# 2_4_-V1.net
KiCad netlist of a schematic drawn in Altium Designer
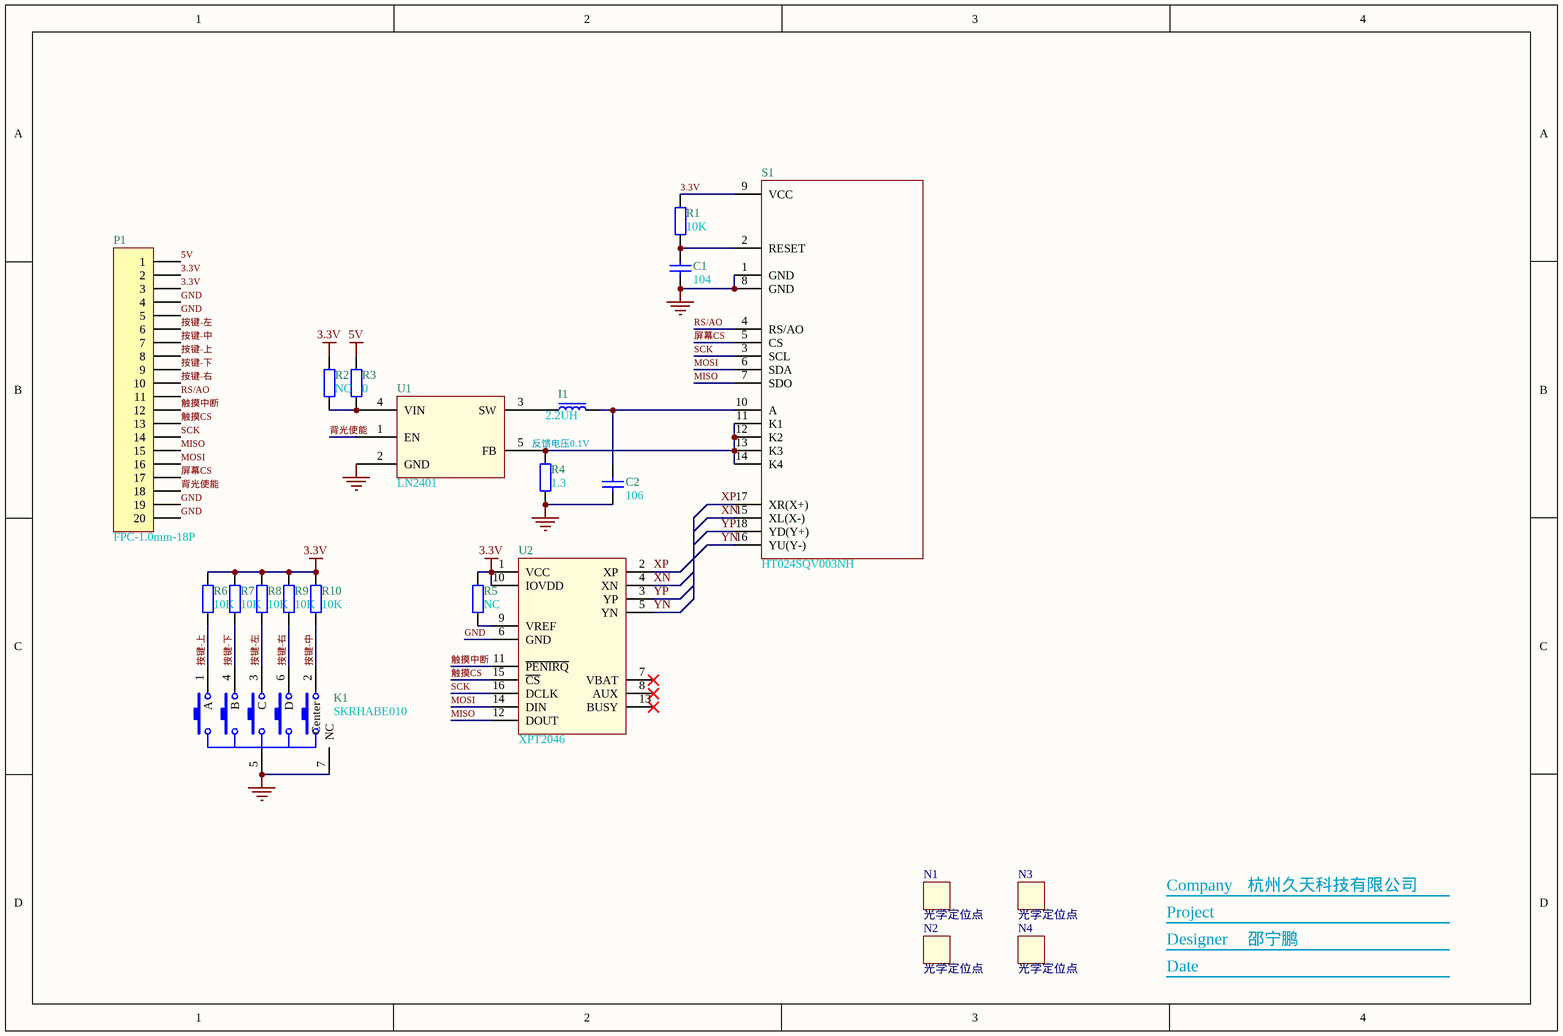
[diagram p0: 2.4寸液晶屏-V1.SchDoc]

(export (version "E")
  (design (tool "Eeschema 10.0.6"))
  (components
    (comp (ref "C1")
      (value "104")
      (footprint "C-0603")
      (description "0805")
      (fields (field (name "PUBLISHER") "Altium Limited"))
      (libsource (lib "2电容-V1.0") (part "Cap-0603"))
    )
    (comp (ref "C2")
      (value "106")
      (footprint "C-0603")
      (description "0805")
      (fields (field (name "PUBLISHER") "Altium Limited"))
      (libsource (lib "2电容-V1.0") (part "Cap-0805"))
    )
    (comp (ref "I1")
      (value "2.2UH")
      (footprint "一体成型电感0420")
      (libsource (lib "3电感-V1.0") (part "Inductance3"))
    )
    (comp (ref "K1")
      (value "SKRHABE010")
      (footprint "SKRHABE010")
      (description "五向开关")
      (libsource (lib "开关-V1") (part "SKRHABE010"))
    )
    (comp (ref "N1") (value "光学定位点") (footprint "MARK-1mm-3mm") (libsource (lib "11其他元件-V1.0") (part "无引脚")))
    (comp (ref "N2") (value "光学定位点") (footprint "MARK-1mm-3mm") (libsource (lib "11其他元件-V1.0") (part "无引脚")))
    (comp (ref "N3") (value "光学定位点") (footprint "MARK-1mm-3mm") (libsource (lib "11其他元件-V1.0") (part "无引脚")))
    (comp (ref "N4") (value "光学定位点") (footprint "MARK-1mm-3mm") (libsource (lib "11其他元件-V1.0") (part "无引脚")))
    (comp (ref "P1")
      (value "FPC-1.0mm-18P")
      (footprint "FPC-1.0mm_18P下接翻盖")
      (description "Header, 20-Pin")
      (fields (field (name "PUBLISHER") "Altium Limited"))
      (libsource (lib "5排针-V1.0") (part "Header 20"))
    )
    (comp (ref "R1")
      (value "10K")
      (footprint "R-0603")
      (description "0603")
      (fields (field (name "PUBLISHER") "Altium Limited"))
      (libsource (lib "1电阻-V1.0") (part "Res2-0603"))
    )
    (comp (ref "R2")
      (value "NC")
      (footprint "R-0603")
      (description "0603")
      (fields (field (name "PUBLISHER") "Altium Limited"))
      (libsource (lib "1电阻-V1.0") (part "Res2-0603"))
    )
    (comp (ref "R3")
      (value "0")
      (footprint "R-0603")
      (description "0603")
      (fields (field (name "PUBLISHER") "Altium Limited"))
      (libsource (lib "1电阻-V1.0") (part "Res2-0603"))
    )
    (comp (ref "R4")
      (value "1.3")
      (footprint "R-0603")
      (description "0805")
      (fields (field (name "PUBLISHER") "Altium Limited"))
      (libsource (lib "1电阻-V1.0") (part "Res2"))
    )
    (comp (ref "R5")
      (value "NC")
      (footprint "R-0603")
      (description "0603")
      (fields (field (name "PUBLISHER") "Altium Limited"))
      (libsource (lib "") (part "Res2-0603_1"))
    )
    (comp (ref "R6")
      (value "10K")
      (footprint "R-0603")
      (description "0603")
      (fields (field (name "PUBLISHER") "Altium Limited"))
      (libsource (lib "1电阻-V1.0") (part "Res2-0603"))
    )
    (comp (ref "R7")
      (value "10K")
      (footprint "R-0603")
      (description "0603")
      (fields (field (name "PUBLISHER") "Altium Limited"))
      (libsource (lib "1电阻-V1.0") (part "Res2-0603"))
    )
    (comp (ref "R8")
      (value "10K")
      (footprint "R-0603")
      (description "0603")
      (fields (field (name "PUBLISHER") "Altium Limited"))
      (libsource (lib "1电阻-V1.0") (part "Res2-0603"))
    )
    (comp (ref "R9")
      (value "10K")
      (footprint "R-0603")
      (description "0603")
      (fields (field (name "PUBLISHER") "Altium Limited"))
      (libsource (lib "1电阻-V1.0") (part "Res2-0603"))
    )
    (comp (ref "R10")
      (value "10K")
      (footprint "R-0603")
      (description "0603")
      (fields (field (name "PUBLISHER") "Altium Limited"))
      (libsource (lib "1电阻-V1.0") (part "Res2-0603"))
    )
    (comp (ref "S1")
      (value "HT024SQV003NH")
      (footprint "HT024SQV003NH")
      (libsource (lib "7显示屏-V1.0") (part "HT024SQV003NH"))
    )
    (comp (ref "U1")
      (value "LN2401")
      (footprint "SOT-23-5-n")
      (description "DC-DC降压")
      (libsource (lib "电源芯片DC-DC") (part "PAM2804"))
    )
    (comp (ref "U2") (value "XPT2046") (footprint "TSSOP-16") (libsource (lib "8集成电路-V1.1") (part "XPT2046")))
  )
  (nets
    (net (code "1") (name "/MISO") (class "Default")
      (node (ref "P1") (pin "15") (pinfunction "15_15") (pintype "passive"))
      (node (ref "S1") (pin "7") (pinfunction "SDO_7") (pintype "passive"))
      (node (ref "U2") (pin "12") (pinfunction "DOUT_12") (pintype "passive"))
    )
    (net (code "2") (name "/MOSI") (class "Default")
      (node (ref "P1") (pin "16") (pinfunction "16_16") (pintype "passive"))
      (node (ref "S1") (pin "6") (pinfunction "SDA_6") (pintype "passive"))
      (node (ref "U2") (pin "14") (pinfunction "DIN_14") (pintype "passive"))
    )
    (net (code "3") (name "/RS{slash}AO") (class "Default")
      (node (ref "P1") (pin "11") (pinfunction "11_11") (pintype "passive"))
      (node (ref "S1") (pin "4") (pinfunction "RS/AO_4") (pintype "passive"))
    )
    (net (code "4") (name "/SCK") (class "Default")
      (node (ref "P1") (pin "14") (pinfunction "14_14") (pintype "passive"))
      (node (ref "S1") (pin "3") (pinfunction "SCL_3") (pintype "passive"))
      (node (ref "U2") (pin "16") (pinfunction "DCLK_16") (pintype "passive"))
    )
    (net (code "5") (name "/XN") (class "Default")
      (node (ref "S1") (pin "15") (pinfunction "XL(X-)_15") (pintype "passive"))
      (node (ref "U2") (pin "4") (pinfunction "XN_4") (pintype "passive"))
    )
    (net (code "6") (name "/XP") (class "Default")
      (node (ref "S1") (pin "17") (pinfunction "XR(X+)_17") (pintype "passive"))
      (node (ref "U2") (pin "2") (pinfunction "XP_2") (pintype "passive"))
    )
    (net (code "7") (name "/YN") (class "Default")
      (node (ref "S1") (pin "16") (pinfunction "YU(Y-)_16") (pintype "passive"))
      (node (ref "U2") (pin "5") (pinfunction "YN_5") (pintype "passive"))
    )
    (net (code "8") (name "/YP") (class "Default")
      (node (ref "S1") (pin "18") (pinfunction "YD(Y+)_18") (pintype "passive"))
      (node (ref "U2") (pin "3") (pinfunction "YP_3") (pintype "passive"))
    )
    (net (code "9") (name "/屏幕CS") (class "Default")
      (node (ref "P1") (pin "17") (pinfunction "17_17") (pintype "passive"))
      (node (ref "S1") (pin "5") (pinfunction "CS_5") (pintype "passive"))
    )
    (net (code "10") (name "/按键-上") (class "Default")
      (node (ref "K1") (pin "1") (pinfunction "A_1") (pintype "passive"))
      (node (ref "P1") (pin "8") (pinfunction "8_8") (pintype "passive"))
      (node (ref "R6") (pin "1") (pinfunction "1_1") (pintype "passive"))
    )
    (net (code "11") (name "/按键-下") (class "Default")
      (node (ref "K1") (pin "4") (pinfunction "B_4") (pintype "passive"))
      (node (ref "P1") (pin "9") (pinfunction "9_9") (pintype "passive"))
      (node (ref "R7") (pin "1") (pinfunction "1_1") (pintype "passive"))
    )
    (net (code "12") (name "/按键-中") (class "Default")
      (node (ref "K1") (pin "2") (pinfunction "Center_2") (pintype "passive"))
      (node (ref "P1") (pin "7") (pinfunction "7_7") (pintype "passive"))
      (node (ref "R10") (pin "1") (pinfunction "1_1") (pintype "passive"))
    )
    (net (code "13") (name "/按键-右") (class "Default")
      (node (ref "K1") (pin "6") (pinfunction "D_6") (pintype "passive"))
      (node (ref "P1") (pin "10") (pinfunction "10_10") (pintype "passive"))
      (node (ref "R9") (pin "1") (pinfunction "1_1") (pintype "passive"))
    )
    (net (code "14") (name "/按键-左") (class "Default")
      (node (ref "K1") (pin "3") (pinfunction "C_3") (pintype "passive"))
      (node (ref "P1") (pin "6") (pinfunction "6_6") (pintype "passive"))
      (node (ref "R8") (pin "1") (pinfunction "1_1") (pintype "passive"))
    )
    (net (code "15") (name "/背光使能") (class "Default")
      (node (ref "P1") (pin "18") (pinfunction "18_18") (pintype "passive"))
      (node (ref "U1") (pin "1") (pinfunction "EN_1") (pintype "passive"))
    )
    (net (code "16") (name "/触摸CS") (class "Default")
      (node (ref "P1") (pin "13") (pinfunction "13_13") (pintype "passive"))
      (node (ref "U2") (pin "15") (pinfunction "~{CS}_15") (pintype "passive"))
    )
    (net (code "17") (name "/触摸中断") (class "Default")
      (node (ref "P1") (pin "12") (pinfunction "12_12") (pintype "passive"))
      (node (ref "U2") (pin "11") (pinfunction "~{PENIRQ}_11") (pintype "passive"))
    )
    (net (code "18") (name "3.3V") (class "Default")
      (node (ref "P1") (pin "2") (pinfunction "2_2") (pintype "passive"))
      (node (ref "P1") (pin "3") (pinfunction "3_3") (pintype "passive"))
      (node (ref "R1") (pin "2") (pinfunction "2_2") (pintype "passive"))
      (node (ref "R10") (pin "2") (pinfunction "2_2") (pintype "passive"))
      (node (ref "R2") (pin "2") (pinfunction "2_2") (pintype "passive"))
      (node (ref "R5") (pin "1") (pinfunction "1_1") (pintype "passive"))
      (node (ref "R6") (pin "2") (pinfunction "2_2") (pintype "passive"))
      (node (ref "R7") (pin "2") (pinfunction "2_2") (pintype "passive"))
      (node (ref "R8") (pin "2") (pinfunction "2_2") (pintype "passive"))
      (node (ref "R9") (pin "2") (pinfunction "2_2") (pintype "passive"))
      (node (ref "S1") (pin "9") (pinfunction "VCC_9") (pintype "passive"))
      (node (ref "U2") (pin "1") (pinfunction "VCC_1") (pintype "passive"))
      (node (ref "U2") (pin "10") (pinfunction "IOVDD_10") (pintype "passive"))
    )
    (net (code "19") (name "5V") (class "Default")
      (node (ref "P1") (pin "1") (pinfunction "1_1") (pintype "passive"))
      (node (ref "R3") (pin "2") (pinfunction "2_2") (pintype "passive"))
    )
    (net (code "20") (name "GND") (class "Default")
      (node (ref "C1") (pin "1") (pinfunction "1_1") (pintype "passive"))
      (node (ref "C2") (pin "1") (pinfunction "1_1") (pintype "passive"))
      (node (ref "K1") (pin "5") (pinfunction "Common_5") (pintype "passive"))
      (node (ref "K1") (pin "7") (pinfunction "NC_7") (pintype "passive"))
      (node (ref "P1") (pin "19") (pinfunction "19_19") (pintype "passive"))
      (node (ref "P1") (pin "20") (pinfunction "20_20") (pintype "passive"))
      (node (ref "P1") (pin "4") (pinfunction "4_4") (pintype "passive"))
      (node (ref "P1") (pin "5") (pinfunction "5_5") (pintype "passive"))
      (node (ref "R4") (pin "1") (pinfunction "1_1") (pintype "passive"))
      (node (ref "S1") (pin "1") (pinfunction "GND_1") (pintype "passive"))
      (node (ref "S1") (pin "8") (pinfunction "GND_8") (pintype "passive"))
      (node (ref "U1") (pin "2") (pinfunction "GND_2") (pintype "passive"))
      (node (ref "U2") (pin "6") (pinfunction "GND_6") (pintype "passive"))
    )
    (net (code "21") (name "Net-(S1-A)") (class "Default")
      (node (ref "C2") (pin "2") (pinfunction "2_2") (pintype "passive"))
      (node (ref "I1") (pin "2") (pinfunction "2_2") (pintype "passive"))
      (node (ref "S1") (pin "10") (pinfunction "A_10") (pintype "passive"))
    )
    (net (code "22") (name "Net-(S1-K1)") (class "Default")
      (node (ref "R4") (pin "2") (pinfunction "2_2") (pintype "passive"))
      (node (ref "S1") (pin "11") (pinfunction "K1_11") (pintype "passive"))
      (node (ref "S1") (pin "12") (pinfunction "K2_12") (pintype "passive"))
      (node (ref "S1") (pin "13") (pinfunction "K3_13") (pintype "passive"))
      (node (ref "S1") (pin "14") (pinfunction "K4_14") (pintype "passive"))
      (node (ref "U1") (pin "5") (pinfunction "FB_5") (pintype "passive"))
    )
    (net (code "23") (name "Net-(S1-RESET)") (class "Default")
      (node (ref "C1") (pin "2") (pinfunction "2_2") (pintype "passive"))
      (node (ref "R1") (pin "1") (pinfunction "1_1") (pintype "passive"))
      (node (ref "S1") (pin "2") (pinfunction "RESET_2") (pintype "passive"))
    )
    (net (code "24") (name "Net-(U1-SW)") (class "Default")
      (node (ref "I1") (pin "1") (pinfunction "1_1") (pintype "passive"))
      (node (ref "U1") (pin "3") (pinfunction "SW_3") (pintype "passive"))
    )
    (net (code "25") (name "Net-(U1-VIN)") (class "Default")
      (node (ref "R2") (pin "1") (pinfunction "1_1") (pintype "passive"))
      (node (ref "R3") (pin "1") (pinfunction "1_1") (pintype "passive"))
      (node (ref "U1") (pin "4") (pinfunction "VIN_4") (pintype "passive"))
    )
    (net (code "26") (name "Net-(U2-VREF)") (class "Default")
      (node (ref "R5") (pin "2") (pinfunction "2_2") (pintype "passive"))
      (node (ref "U2") (pin "9") (pinfunction "VREF_9") (pintype "passive"))
    )
    (net (code "27") (name "unconnected-(U2-AUX-Pad8)") (class "Default")
      (node (ref "U2") (pin "8") (pinfunction "AUX_8") (pintype "passive+no_connect"))
    )
    (net (code "28") (name "unconnected-(U2-BUSY-Pad13)") (class "Default")
      (node (ref "U2") (pin "13") (pinfunction "BUSY_13") (pintype "passive+no_connect"))
    )
    (net (code "29") (name "unconnected-(U2-VBAT-Pad7)") (class "Default")
      (node (ref "U2") (pin "7") (pinfunction "VBAT_7") (pintype "passive+no_connect"))
    )
  )
)
